# usb-dip-switch.net
KiCad netlist of a schematic drawn in EAGLE
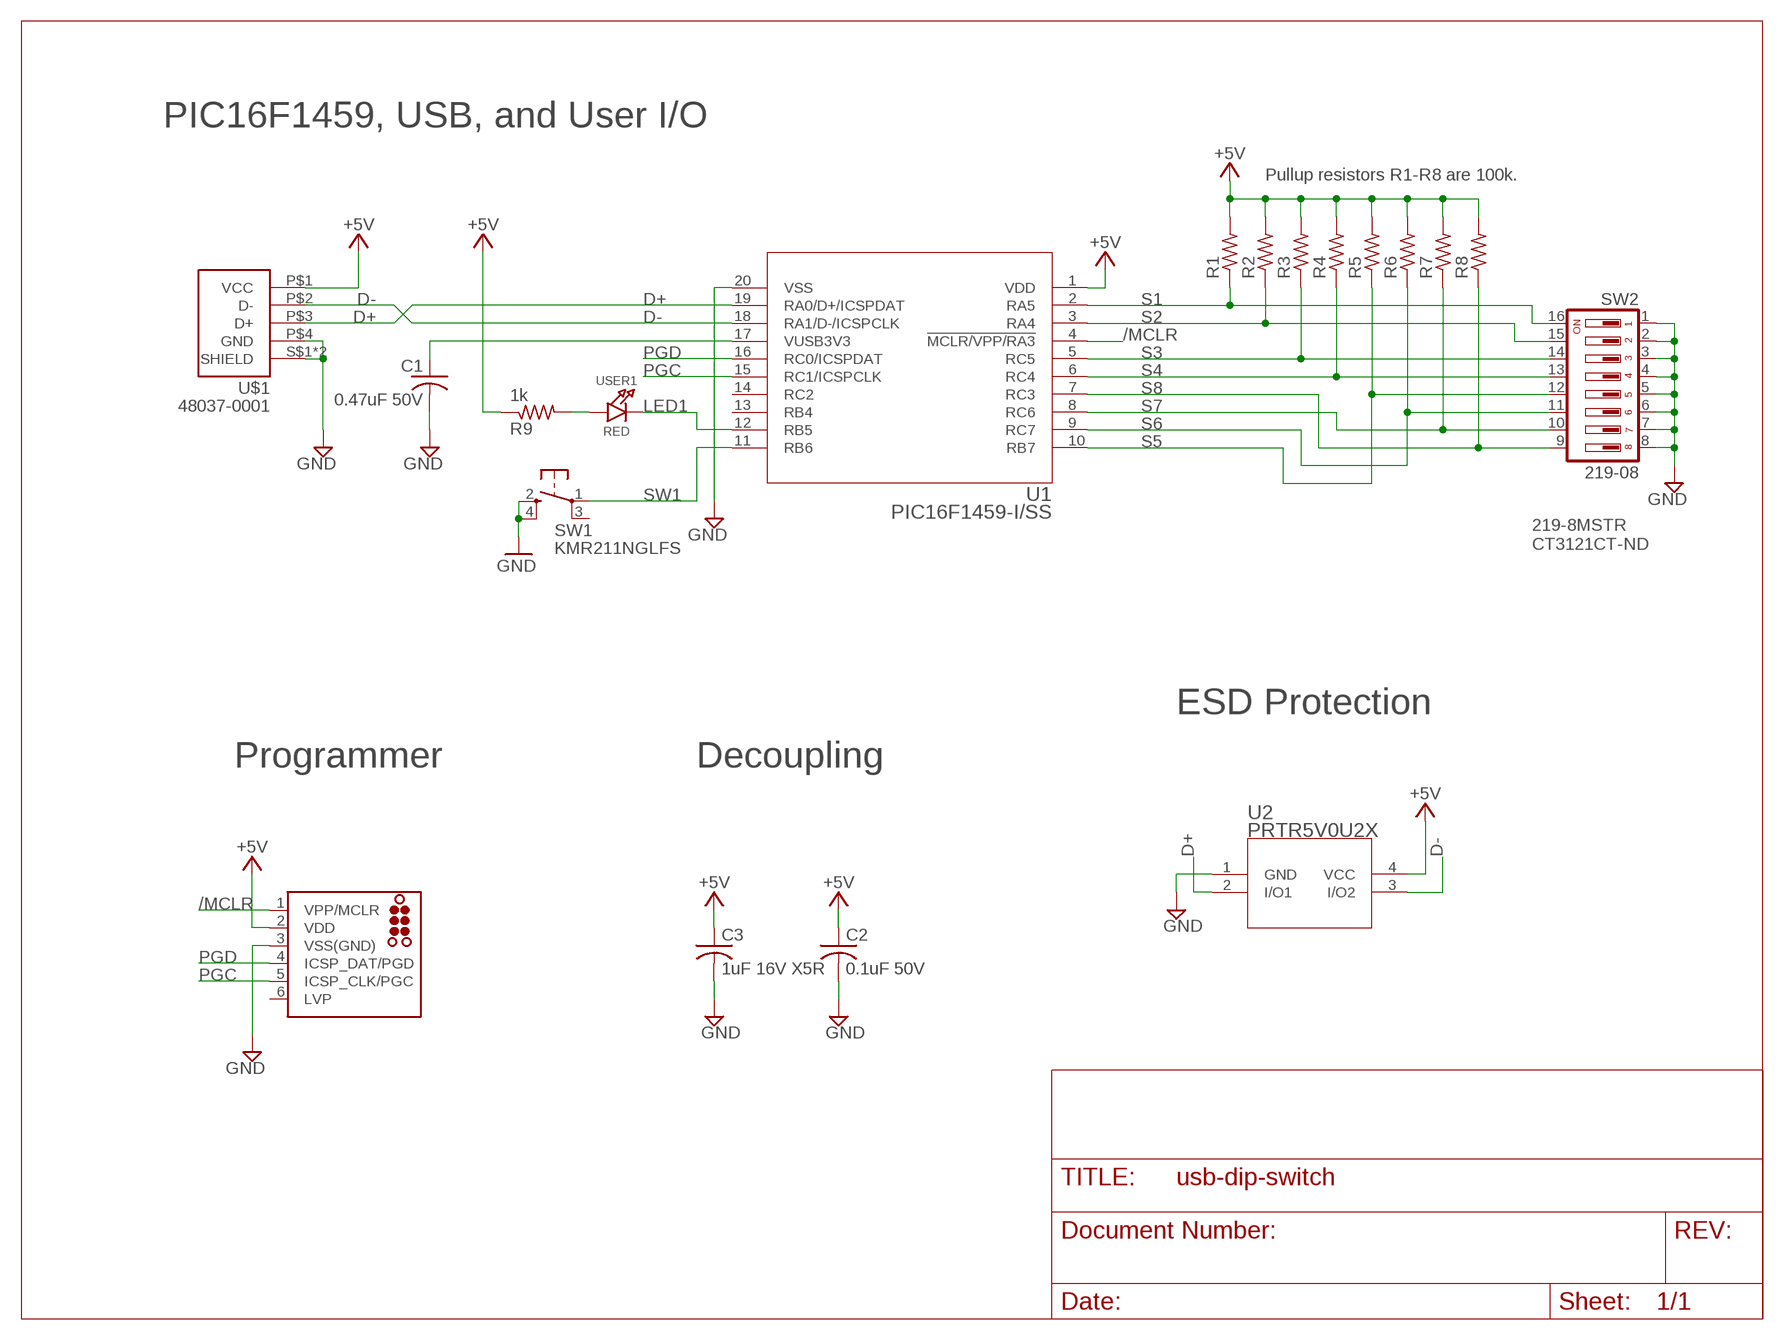
[diagram p0: schematic, sheet 1]

(export (version "E")
  (design (tool "Eeschema 10.0.6"))
  (components
    (comp (ref "C1")
      (value "0.47uF 50V")
      (footprint "eagle-import:C1206K")
      (fields (field (name "MFR") "KEMET") (field (name "MFR_PART_NO") "C1206C474K5RACTU"))
      (libsource (lib "eagle-import") (part "C-USC1206K"))
    )
    (comp (ref "C2")
      (value "0.1uF 50V")
      (footprint "eagle-import:C0603")
      (fields (field (name "MFR") "KEMET") (field (name "MFR_PART_NO") "C1206S104M5RACTU"))
      (libsource (lib "eagle-import") (part "C-USC0603"))
    )
    (comp (ref "C3")
      (value "1uF 16V X5R")
      (footprint "eagle-import:C0603")
      (fields (field (name "MFR") "KEMET") (field (name "MFR_PART_NO") "C1210C105K4PACTU"))
      (libsource (lib "eagle-import") (part "C-USC0603"))
    )
    (comp (ref "J3")
      (value "TC2030-MCP-NL")
      (footprint "eagle-import:TC2030-MCP-NL")
      (libsource (lib "eagle-import") (part "TC2030-MCP-NL"))
    )
    (comp (ref "R1")
      (value "100k")
      (footprint "eagle-import:R0603")
      (libsource (lib "eagle-import") (part "R-US_R0603"))
    )
    (comp (ref "R2")
      (value "100k")
      (footprint "eagle-import:R0603")
      (libsource (lib "eagle-import") (part "R-US_R0603"))
    )
    (comp (ref "R3")
      (value "100k")
      (footprint "eagle-import:R0603")
      (libsource (lib "eagle-import") (part "R-US_R0603"))
    )
    (comp (ref "R4")
      (value "100k")
      (footprint "eagle-import:R0603")
      (libsource (lib "eagle-import") (part "R-US_R0603"))
    )
    (comp (ref "R5")
      (value "100k")
      (footprint "eagle-import:R0603")
      (libsource (lib "eagle-import") (part "R-US_R0603"))
    )
    (comp (ref "R6")
      (value "100k")
      (footprint "eagle-import:R0603")
      (libsource (lib "eagle-import") (part "R-US_R0603"))
    )
    (comp (ref "R7")
      (value "100k")
      (footprint "eagle-import:R0603")
      (libsource (lib "eagle-import") (part "R-US_R0603"))
    )
    (comp (ref "R8")
      (value "100k")
      (footprint "eagle-import:R0603")
      (libsource (lib "eagle-import") (part "R-US_R0603"))
    )
    (comp (ref "R9")
      (value "1k")
      (footprint "eagle-import:R0805")
      (libsource (lib "eagle-import") (part "R-US_R0805"))
    )
    (comp (ref "SW1")
      (value "KMR211NGLFS")
      (footprint "eagle-import:KMR2")
      (libsource (lib "eagle-import") (part "SPST_TACT-KMR2"))
    )
    (comp (ref "SW2")
      (value "219-08")
      (footprint "eagle-import:CTS-219-08")
      (libsource (lib "eagle-import") (part "219-08"))
    )
    (comp (ref "U$1")
      (value "48037-0001")
      (footprint "eagle-import:48037-0001")
      (libsource (lib "eagle-import") (part "48037-0001"))
    )
    (comp (ref "U1")
      (value "PIC16F1459-I/SS")
      (footprint "eagle-import:SSOP20_MC")
      (fields (field (name "MANUFACTURER_PART_NUMBER") "PIC16F1459ISS"))
      (libsource (lib "eagle-import") (part "PIC16F1459-I/SS"))
    )
    (comp (ref "U2")
      (value "PRTR5V0U2X")
      (footprint "eagle-import:SOT143B")
      (libsource (lib "eagle-import") (part "PRTR5V0U2X"))
    )
    (comp (ref "USER1")
      (value "RED")
      (footprint "eagle-import:CHIPLED_0805_NOOUTLINE")
      (libsource (lib "eagle-import") (part "LED0805_NOOUTLINE"))
    )
  )
  (nets
    (net (code "1") (name "+5V") (class "Default")
      (node (ref "C2") (pin "1") (pinfunction "1_1") (pintype "passive"))
      (node (ref "C3") (pin "1") (pinfunction "1_1") (pintype "passive"))
      (node (ref "J3") (pin "2") (pinfunction "VDD_2") (pintype "power_in"))
      (node (ref "R1") (pin "2") (pinfunction "2_2") (pintype "passive"))
      (node (ref "R2") (pin "2") (pinfunction "2_2") (pintype "passive"))
      (node (ref "R3") (pin "2") (pinfunction "2_2") (pintype "passive"))
      (node (ref "R4") (pin "2") (pinfunction "2_2") (pintype "passive"))
      (node (ref "R5") (pin "2") (pinfunction "2_2") (pintype "passive"))
      (node (ref "R6") (pin "2") (pinfunction "2_2") (pintype "passive"))
      (node (ref "R7") (pin "2") (pinfunction "2_2") (pintype "passive"))
      (node (ref "R8") (pin "2") (pinfunction "2_2") (pintype "passive"))
      (node (ref "R9") (pin "1") (pinfunction "1_1") (pintype "passive"))
      (node (ref "U$1") (pin "P$1") (pinfunction "VCC_P$1") (pintype "bidirectional"))
      (node (ref "U1") (pin "1") (pinfunction "VDD_1") (pintype "power_in"))
      (node (ref "U2") (pin "4") (pinfunction "VCC_4") (pintype "passive"))
    )
    (net (code "2") (name "/D+") (class "Default")
      (node (ref "U$1") (pin "P$3") (pinfunction "D+_P$3") (pintype "bidirectional"))
      (node (ref "U1") (pin "19") (pinfunction "RA0/D+/ICSPDAT_19") (pintype "bidirectional"))
      (node (ref "U2") (pin "2") (pinfunction "I/O1_2") (pintype "passive"))
    )
    (net (code "3") (name "/D-") (class "Default")
      (node (ref "U$1") (pin "P$2") (pinfunction "D-_P$2") (pintype "bidirectional"))
      (node (ref "U1") (pin "18") (pinfunction "RA1/D-/ICSPCLK_18") (pintype "bidirectional"))
      (node (ref "U2") (pin "3") (pinfunction "I/O2_3") (pintype "passive"))
    )
    (net (code "4") (name "/LED1") (class "Default")
      (node (ref "U1") (pin "12") (pinfunction "RB5_12") (pintype "bidirectional"))
      (node (ref "USER1") (pin "C") (pinfunction "C_C") (pintype "passive"))
    )
    (net (code "5") (name "/PGC") (class "Default")
      (node (ref "J3") (pin "5") (pinfunction "ICSP_CLK/PGC_5") (pintype "output"))
      (node (ref "U1") (pin "15") (pinfunction "RC1/ICSPCLK_15") (pintype "bidirectional"))
    )
    (net (code "6") (name "/PGD") (class "Default")
      (node (ref "J3") (pin "4") (pinfunction "ICSP_DAT/PGD_4") (pintype "bidirectional"))
      (node (ref "U1") (pin "16") (pinfunction "RC0/ICSPDAT_16") (pintype "bidirectional"))
    )
    (net (code "7") (name "/S1") (class "Default")
      (node (ref "R1") (pin "1") (pinfunction "1_1") (pintype "passive"))
      (node (ref "SW2") (pin "16") (pinfunction "16_16") (pintype "passive"))
      (node (ref "U1") (pin "2") (pinfunction "RA5_2") (pintype "bidirectional"))
    )
    (net (code "8") (name "/S2") (class "Default")
      (node (ref "R2") (pin "1") (pinfunction "1_1") (pintype "passive"))
      (node (ref "SW2") (pin "15") (pinfunction "15_15") (pintype "passive"))
      (node (ref "U1") (pin "3") (pinfunction "RA4_3") (pintype "bidirectional"))
    )
    (net (code "9") (name "/S3") (class "Default")
      (node (ref "R3") (pin "1") (pinfunction "1_1") (pintype "passive"))
      (node (ref "SW2") (pin "14") (pinfunction "14_14") (pintype "passive"))
      (node (ref "U1") (pin "5") (pinfunction "RC5_5") (pintype "bidirectional"))
    )
    (net (code "10") (name "/S4") (class "Default")
      (node (ref "R4") (pin "1") (pinfunction "1_1") (pintype "passive"))
      (node (ref "SW2") (pin "13") (pinfunction "13_13") (pintype "passive"))
      (node (ref "U1") (pin "6") (pinfunction "RC4_6") (pintype "bidirectional"))
    )
    (net (code "11") (name "/S5") (class "Default")
      (node (ref "R5") (pin "1") (pinfunction "1_1") (pintype "passive"))
      (node (ref "SW2") (pin "12") (pinfunction "12_12") (pintype "passive"))
      (node (ref "U1") (pin "10") (pinfunction "RB7_10") (pintype "bidirectional"))
    )
    (net (code "12") (name "/S6") (class "Default")
      (node (ref "R6") (pin "1") (pinfunction "1_1") (pintype "passive"))
      (node (ref "SW2") (pin "11") (pinfunction "11_11") (pintype "passive"))
      (node (ref "U1") (pin "9") (pinfunction "RC7_9") (pintype "bidirectional"))
    )
    (net (code "13") (name "/S7") (class "Default")
      (node (ref "R7") (pin "1") (pinfunction "1_1") (pintype "passive"))
      (node (ref "SW2") (pin "10") (pinfunction "10_10") (pintype "passive"))
      (node (ref "U1") (pin "8") (pinfunction "RC6_8") (pintype "bidirectional"))
    )
    (net (code "14") (name "/S8") (class "Default")
      (node (ref "R8") (pin "1") (pinfunction "1_1") (pintype "passive"))
      (node (ref "SW2") (pin "9") (pinfunction "9_9") (pintype "passive"))
      (node (ref "U1") (pin "7") (pinfunction "RC3_7") (pintype "bidirectional"))
    )
    (net (code "15") (name "/SW1") (class "Default")
      (node (ref "SW1") (pin "1") (pinfunction "P_1") (pintype "passive"))
      (node (ref "U1") (pin "11") (pinfunction "RB6_11") (pintype "bidirectional"))
    )
    (net (code "16") (name "/{slash}MCLR") (class "Default")
      (node (ref "J3") (pin "1") (pinfunction "VPP/MCLR_1") (pintype "passive"))
      (node (ref "U1") (pin "4") (pinfunction "~{MCLR/VPP/RA3}_4") (pintype "bidirectional"))
    )
    (net (code "17") (name "GND") (class "Default")
      (node (ref "C1") (pin "2") (pinfunction "2_2") (pintype "passive"))
      (node (ref "C2") (pin "2") (pinfunction "2_2") (pintype "passive"))
      (node (ref "C3") (pin "2") (pinfunction "2_2") (pintype "passive"))
      (node (ref "J3") (pin "3") (pinfunction "VSS(GND)_3") (pintype "power_in"))
      (node (ref "SW1") (pin "2") (pinfunction "S_2") (pintype "passive"))
      (node (ref "SW1") (pin "4") (pinfunction "S1_4") (pintype "passive"))
      (node (ref "SW2") (pin "1") (pinfunction "1_1") (pintype "passive"))
      (node (ref "SW2") (pin "2") (pinfunction "2_2") (pintype "passive"))
      (node (ref "SW2") (pin "3") (pinfunction "3_3") (pintype "passive"))
      (node (ref "SW2") (pin "4") (pinfunction "4_4") (pintype "passive"))
      (node (ref "SW2") (pin "5") (pinfunction "5_5") (pintype "passive"))
      (node (ref "SW2") (pin "6") (pinfunction "6_6") (pintype "passive"))
      (node (ref "SW2") (pin "7") (pinfunction "7_7") (pintype "passive"))
      (node (ref "SW2") (pin "8") (pinfunction "8_8") (pintype "passive"))
      (node (ref "U$1") (pin "P$4") (pinfunction "GND_P$4") (pintype "bidirectional"))
      (node (ref "U$1") (pin "S$1") (pinfunction "SHIELD_S$1") (pintype "bidirectional"))
      (node (ref "U$1") (pin "S$2") (pinfunction "SHIELD_S$2") (pintype "bidirectional"))
      (node (ref "U1") (pin "20") (pinfunction "VSS_20") (pintype "power_in"))
      (node (ref "U2") (pin "1") (pinfunction "GND_1") (pintype "passive"))
    )
    (net (code "18") (name "Net-(R9-Pad2)") (class "Default")
      (node (ref "R9") (pin "2") (pinfunction "2_2") (pintype "passive"))
      (node (ref "USER1") (pin "A") (pinfunction "A_A") (pintype "passive"))
    )
    (net (code "19") (name "Net-(U1-VUSB3V3)") (class "Default")
      (node (ref "C1") (pin "1") (pinfunction "1_1") (pintype "passive"))
      (node (ref "U1") (pin "17") (pinfunction "VUSB3V3_17") (pintype "power_in"))
    )
    (net (code "20") (name "unconnected-(J3-LVP-Pad6)") (class "Default")
      (node (ref "J3") (pin "6") (pinfunction "LVP_6") (pintype "bidirectional"))
    )
    (net (code "21") (name "unconnected-(SW1-P1-Pad3)") (class "Default")
      (node (ref "SW1") (pin "3") (pinfunction "P1_3") (pintype "passive"))
    )
    (net (code "22") (name "unconnected-(U1-RB4-Pad13)") (class "Default")
      (node (ref "U1") (pin "13") (pinfunction "RB4_13") (pintype "bidirectional"))
    )
    (net (code "23") (name "unconnected-(U1-RC2-Pad14)") (class "Default")
      (node (ref "U1") (pin "14") (pinfunction "RC2_14") (pintype "bidirectional"))
    )
  )
)
